# booster.net
KiCad netlist of a schematic drawn in EAGLE
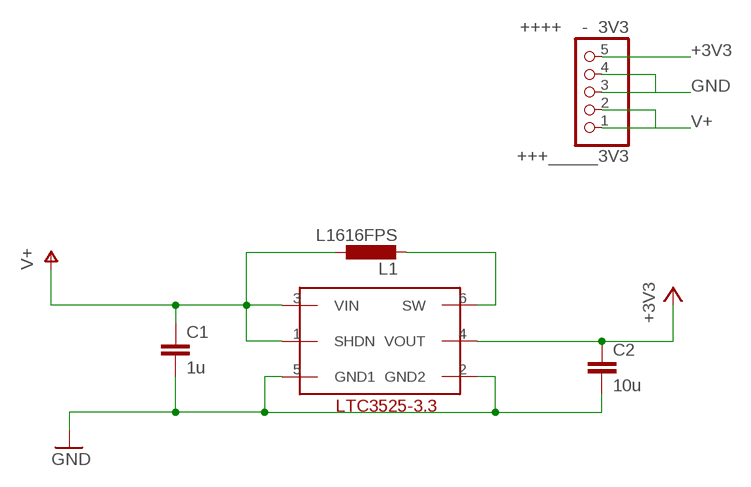
[diagram p0: schematic, sheet 1]

(export (version "E")
  (design (tool "Eeschema 10.0.6"))
  (components
    (comp (ref "+++_____3V3")
      (value "++++ - 3V3")
      (footprint "eagle-import:1X05")
      (libsource (lib "eagle-import") (part "PINHD-1X5"))
    )
    (comp (ref "C1")
      (value "1u")
      (footprint "eagle-import:C0805")
      (libsource (lib "eagle-import") (part "C-EUC0805"))
    )
    (comp (ref "C2")
      (value "10u")
      (footprint "eagle-import:C0805")
      (libsource (lib "eagle-import") (part "C-EUC0805"))
    )
    (comp (ref "IC")
      (value "LTC3525")
      (footprint "eagle-import:TSOT23-6")
      (libsource (lib "eagle-import") (part "LTC3525"))
    )
    (comp (ref "L1")
      (value "L1616FPS")
      (footprint "eagle-import:L1616")
      (libsource (lib "eagle-import") (part "L1616FPS"))
    )
  )
  (nets
    (net (code "1") (name "+3V3") (class "Default")
      (node (ref "+++_____3V3") (pin "5") (pinfunction "5_5") (pintype "passive"))
      (node (ref "C2") (pin "1") (pinfunction "1_1") (pintype "passive"))
      (node (ref "IC") (pin "4") (pinfunction "VOUT_4") (pintype "bidirectional"))
    )
    (net (code "2") (name "GND") (class "Default")
      (node (ref "+++_____3V3") (pin "3") (pinfunction "3_3") (pintype "passive"))
      (node (ref "+++_____3V3") (pin "4") (pinfunction "4_4") (pintype "passive"))
      (node (ref "C1") (pin "2") (pinfunction "2_2") (pintype "passive"))
      (node (ref "C2") (pin "2") (pinfunction "2_2") (pintype "passive"))
      (node (ref "IC") (pin "2") (pinfunction "GND2_2") (pintype "bidirectional"))
      (node (ref "IC") (pin "5") (pinfunction "GND1_5") (pintype "bidirectional"))
    )
    (net (code "3") (name "Net-(IC-SW)") (class "Default")
      (node (ref "IC") (pin "6") (pinfunction "SW_6") (pintype "bidirectional"))
      (node (ref "L1") (pin "P$2") (pinfunction "2_P$2") (pintype "passive"))
    )
    (net (code "4") (name "V+") (class "Default")
      (node (ref "+++_____3V3") (pin "1") (pinfunction "1_1") (pintype "passive"))
      (node (ref "+++_____3V3") (pin "2") (pinfunction "2_2") (pintype "passive"))
      (node (ref "C1") (pin "1") (pinfunction "1_1") (pintype "passive"))
      (node (ref "IC") (pin "1") (pinfunction "SHDN_1") (pintype "bidirectional"))
      (node (ref "IC") (pin "3") (pinfunction "VIN_3") (pintype "bidirectional"))
      (node (ref "L1") (pin "P$1") (pinfunction "1_P$1") (pintype "passive"))
    )
  )
)
